# ILX544A_V2_B1.net
KiCad netlist of a schematic drawn in EAGLE
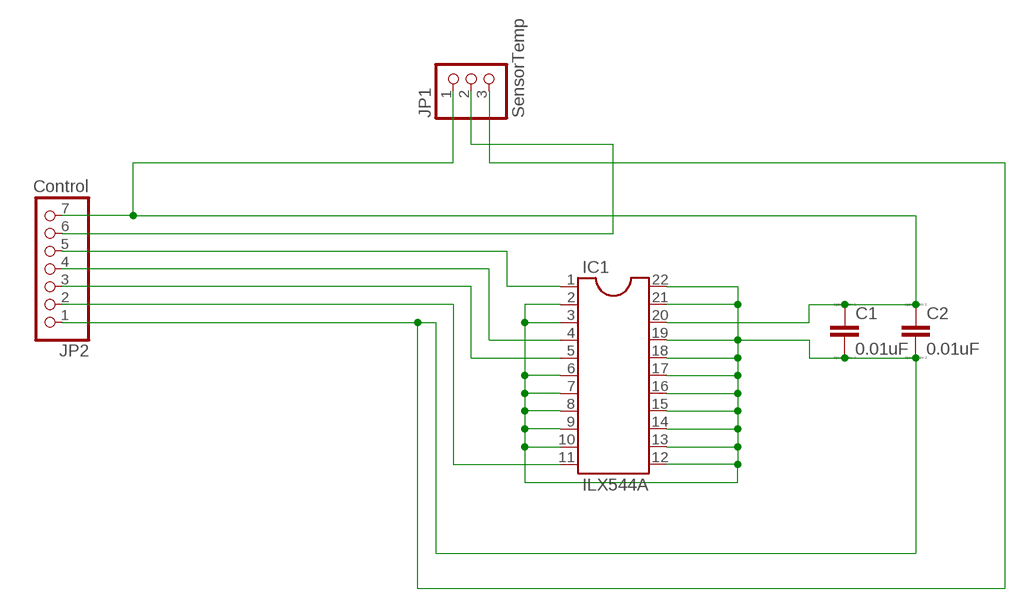
[diagram p0: schematic, sheet 1]

(export (version "E")
  (design (tool "Eeschema 10.0.6"))
  (components
    (comp (ref "C1")
      (value "0.01uF")
      (footprint "eagle-import:C0402")
      (libsource (lib "eagle-import") (part "CC0402"))
    )
    (comp (ref "C2")
      (value "0.01uF")
      (footprint "eagle-import:C0402")
      (libsource (lib "eagle-import") (part "CC0402"))
    )
    (comp (ref "IC1")
      (value "ILX544A")
      (footprint "eagle-import:DIL22-4")
      (libsource (lib "eagle-import") (part "DIL22-4"))
    )
    (comp (ref "JP1")
      (value "SensorTemp")
      (footprint "eagle-import:1X03")
      (libsource (lib "eagle-import") (part "PINHD-1X3"))
    )
    (comp (ref "JP2")
      (value "Control")
      (footprint "eagle-import:1X07")
      (libsource (lib "eagle-import") (part "PINHD-1X7"))
    )
  )
  (nets
    (net (code "1") (name "Net-(C1-Pad1)") (class "Default")
      (node (ref "C1") (pin "1") (pinfunction "1_1") (pintype "passive"))
      (node (ref "C2") (pin "1") (pinfunction "1_1") (pintype "passive"))
      (node (ref "IC1") (pin "20") (pinfunction "20_20") (pintype "passive"))
      (node (ref "JP1") (pin "1") (pinfunction "1_1") (pintype "passive"))
      (node (ref "JP2") (pin "7") (pinfunction "7_7") (pintype "passive"))
    )
    (net (code "2") (name "Net-(C1-Pad2)") (class "Default")
      (node (ref "C1") (pin "2") (pinfunction "2_2") (pintype "passive"))
      (node (ref "C2") (pin "2") (pinfunction "2_2") (pintype "passive"))
      (node (ref "IC1") (pin "10") (pinfunction "10_10") (pintype "passive"))
      (node (ref "IC1") (pin "12") (pinfunction "12_12") (pintype "passive"))
      (node (ref "IC1") (pin "13") (pinfunction "13_13") (pintype "passive"))
      (node (ref "IC1") (pin "14") (pinfunction "14_14") (pintype "passive"))
      (node (ref "IC1") (pin "15") (pinfunction "15_15") (pintype "passive"))
      (node (ref "IC1") (pin "16") (pinfunction "16_16") (pintype "passive"))
      (node (ref "IC1") (pin "17") (pinfunction "17_17") (pintype "passive"))
      (node (ref "IC1") (pin "18") (pinfunction "18_18") (pintype "passive"))
      (node (ref "IC1") (pin "19") (pinfunction "19_19") (pintype "passive"))
      (node (ref "IC1") (pin "2") (pinfunction "2_2") (pintype "passive"))
      (node (ref "IC1") (pin "21") (pinfunction "21_21") (pintype "passive"))
      (node (ref "IC1") (pin "22") (pinfunction "22_22") (pintype "passive"))
      (node (ref "IC1") (pin "3") (pinfunction "3_3") (pintype "passive"))
      (node (ref "IC1") (pin "6") (pinfunction "6_6") (pintype "passive"))
      (node (ref "IC1") (pin "7") (pinfunction "7_7") (pintype "passive"))
      (node (ref "IC1") (pin "8") (pinfunction "8_8") (pintype "passive"))
      (node (ref "IC1") (pin "9") (pinfunction "9_9") (pintype "passive"))
      (node (ref "JP1") (pin "3") (pinfunction "3_3") (pintype "passive"))
      (node (ref "JP2") (pin "1") (pinfunction "1_1") (pintype "passive"))
    )
    (net (code "3") (name "Net-(IC1-Pad1)") (class "Default")
      (node (ref "IC1") (pin "1") (pinfunction "1_1") (pintype "passive"))
      (node (ref "JP2") (pin "5") (pinfunction "5_5") (pintype "passive"))
    )
    (net (code "4") (name "Net-(IC1-Pad4)") (class "Default")
      (node (ref "IC1") (pin "4") (pinfunction "4_4") (pintype "passive"))
      (node (ref "JP2") (pin "4") (pinfunction "4_4") (pintype "passive"))
    )
    (net (code "5") (name "Net-(IC1-Pad5)") (class "Default")
      (node (ref "IC1") (pin "5") (pinfunction "5_5") (pintype "passive"))
      (node (ref "JP2") (pin "3") (pinfunction "3_3") (pintype "passive"))
    )
    (net (code "6") (name "Net-(IC1-Pad11)") (class "Default")
      (node (ref "IC1") (pin "11") (pinfunction "11_11") (pintype "passive"))
      (node (ref "JP2") (pin "2") (pinfunction "2_2") (pintype "passive"))
    )
    (net (code "7") (name "Net-(JP1-Pad2)") (class "Default")
      (node (ref "JP1") (pin "2") (pinfunction "2_2") (pintype "passive"))
      (node (ref "JP2") (pin "6") (pinfunction "6_6") (pintype "passive"))
    )
  )
)
